# MD017A_ISO-F28027F_1.net
KiCad netlist of a schematic drawn in Altium Designer
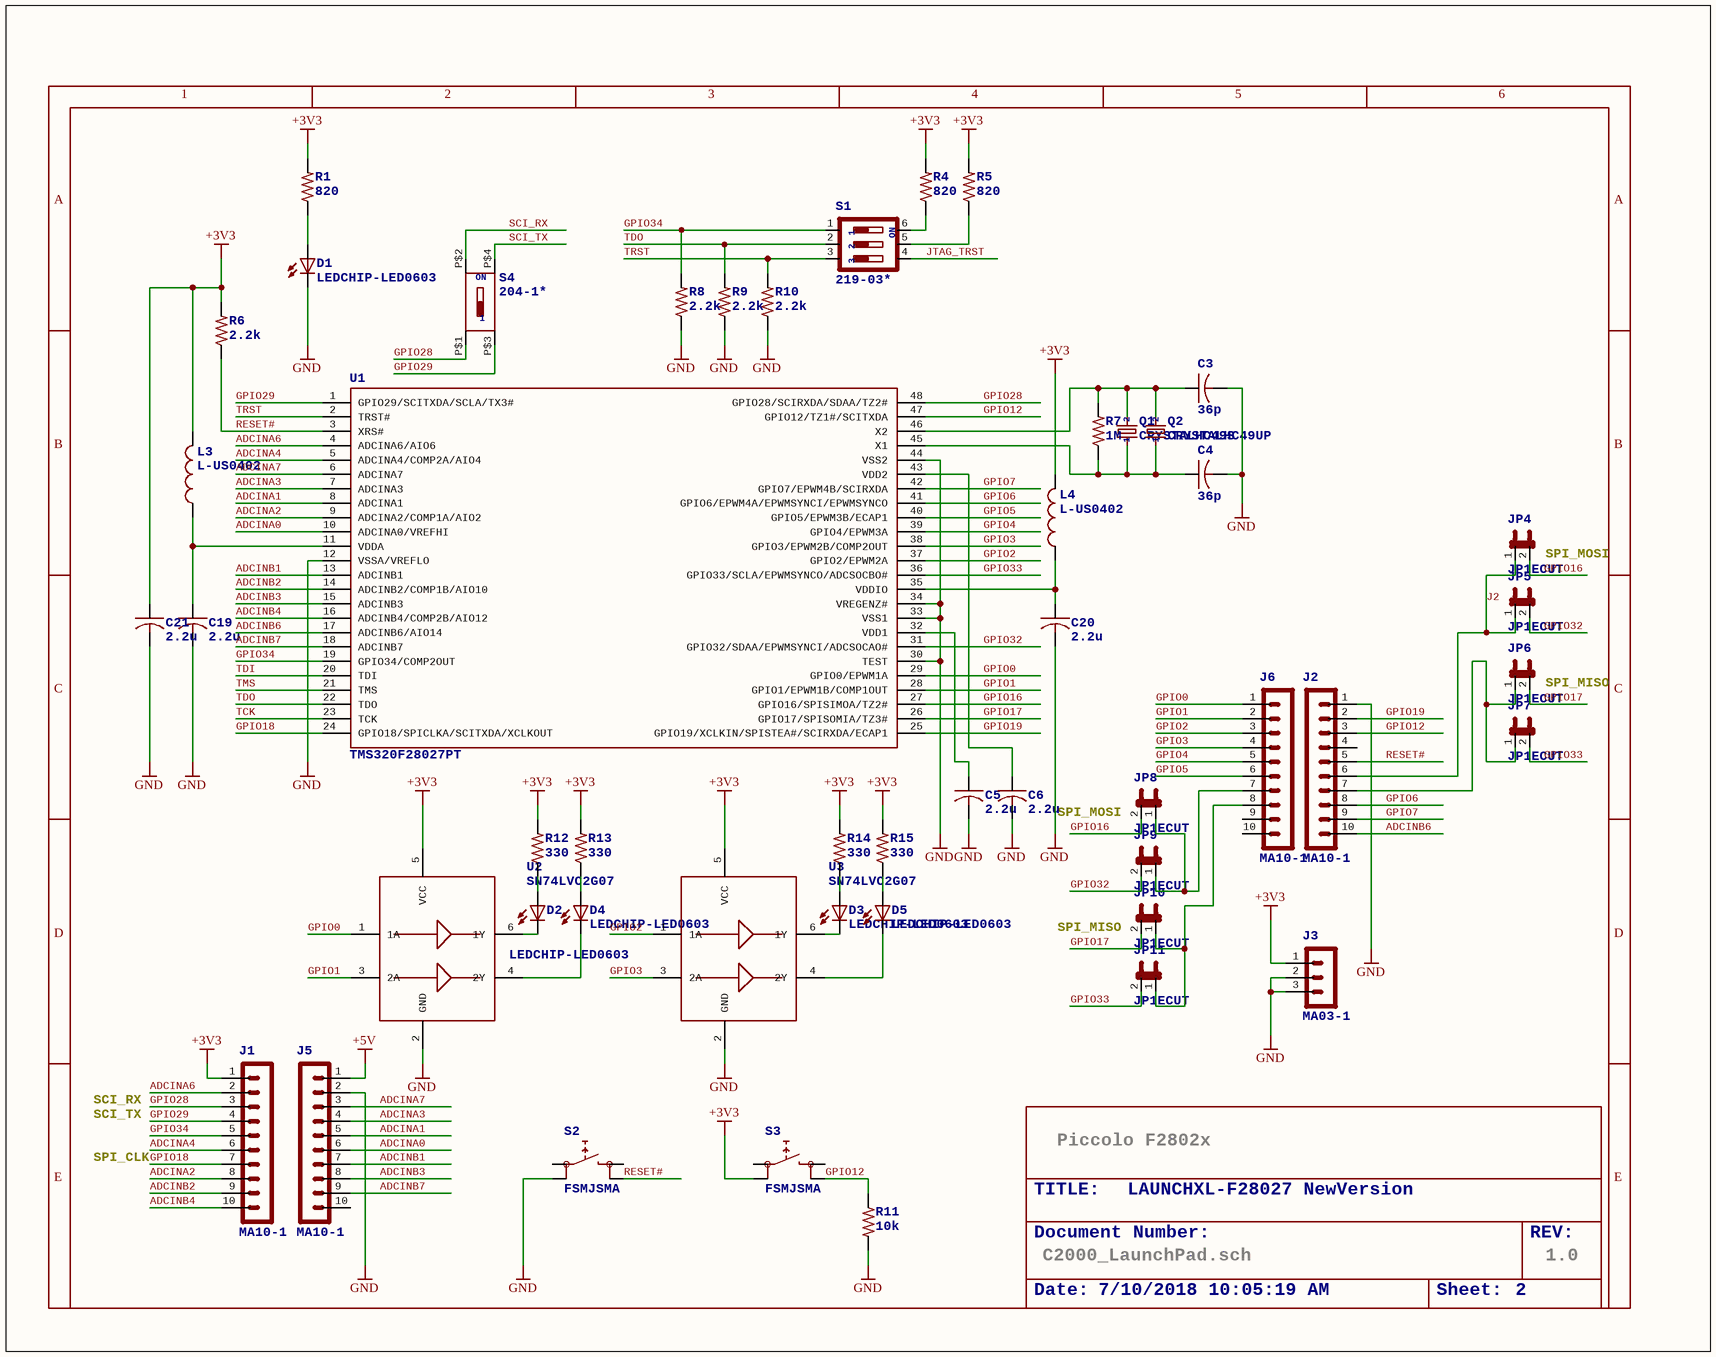
[diagram p0: MD017A ISO-F28027F_1.SchDoc]

(export (version "E")
  (design (tool "Eeschema 10.0.6"))
  (components
    (comp (ref "C3")
      (value "36p")
      (footprint "C0402")
      (description "CAPACITOR, American symbol")
      (libsource (lib "rcl") (part "C-USC0402"))
    )
    (comp (ref "C4")
      (value "36p")
      (footprint "C0402")
      (description "CAPACITOR, American symbol")
      (libsource (lib "rcl") (part "C-USC0402"))
    )
    (comp (ref "C5")
      (value "2.2u")
      (footprint "C0402")
      (description "CAPACITOR, American symbol")
      (libsource (lib "rcl") (part "C-USC0402"))
    )
    (comp (ref "C6")
      (value "2.2u")
      (footprint "C0402")
      (description "CAPACITOR, American symbol")
      (libsource (lib "rcl") (part "C-USC0402"))
    )
    (comp (ref "C19")
      (value "2.2u")
      (footprint "C0402")
      (description "CAPACITOR, American symbol")
      (libsource (lib "rcl") (part "C-USC0402"))
    )
    (comp (ref "C20")
      (value "2.2u")
      (footprint "C0402")
      (description "CAPACITOR, American symbol")
      (libsource (lib "rcl") (part "C-USC0402"))
    )
    (comp (ref "C21")
      (value "2.2u")
      (footprint "C0402")
      (description "CAPACITOR, American symbol")
      (libsource (lib "rcl") (part "C-USC0402"))
    )
    (comp (ref "D1")
      (value "LEDCHIP-LED0603")
      (footprint "CHIP-LED0603")
      (libsource (lib "led") (part "LEDCHIP-LED0603"))
    )
    (comp (ref "D2")
      (value "LEDCHIP-LED0603")
      (footprint "CHIP-LED0603")
      (libsource (lib "led") (part "LEDCHIP-LED0603"))
    )
    (comp (ref "D3")
      (value "LEDCHIP-LED0603")
      (footprint "CHIP-LED0603")
      (libsource (lib "led") (part "LEDCHIP-LED0603"))
    )
    (comp (ref "D4")
      (value "LEDCHIP-LED0603")
      (footprint "CHIP-LED0603")
      (libsource (lib "led") (part "LEDCHIP-LED0603"))
    )
    (comp (ref "D5")
      (value "LEDCHIP-LED0603")
      (footprint "CHIP-LED0603")
      (libsource (lib "led") (part "LEDCHIP-LED0603"))
    )
    (comp (ref "J1")
      (value "MA10-1")
      (footprint "MA10-1")
      (description "PIN HEADER")
      (libsource (lib "con-lstb") (part "MA10-1"))
    )
    (comp (ref "J2")
      (value "MA10-1")
      (footprint "MA10-1")
      (description "PIN HEADER")
      (libsource (lib "con-lstb") (part "MA10-1"))
    )
    (comp (ref "J3")
      (value "MA03-1")
      (footprint "MA03-1")
      (description "PIN HEADER")
      (libsource (lib "con-lstb") (part "MA03-1"))
    )
    (comp (ref "J5")
      (value "MA10-1")
      (footprint "MA10-1")
      (description "PIN HEADER")
      (libsource (lib "con-lstb") (part "MA10-1"))
    )
    (comp (ref "J6")
      (value "MA10-1")
      (footprint "MA10-1")
      (description "PIN HEADER")
      (libsource (lib "con-lstb") (part "MA10-1"))
    )
    (comp (ref "JP4")
      (value "JP1ECUT")
      (footprint "C0402")
      (description "JUMPER")
      (libsource (lib "jumper") (part "JP1ECUT"))
    )
    (comp (ref "JP5")
      (value "JP1ECUT")
      (footprint "C0402")
      (description "JUMPER")
      (libsource (lib "jumper") (part "JP1ECUT"))
    )
    (comp (ref "JP6")
      (value "JP1ECUT")
      (footprint "C0402")
      (description "JUMPER")
      (libsource (lib "jumper") (part "JP1ECUT"))
    )
    (comp (ref "JP7")
      (value "JP1ECUT")
      (footprint "C0402")
      (description "JUMPER")
      (libsource (lib "jumper") (part "JP1ECUT"))
    )
    (comp (ref "JP8")
      (value "JP1ECUT")
      (footprint "C0402")
      (description "JUMPER")
      (libsource (lib "jumper") (part "JP1ECUT"))
    )
    (comp (ref "JP9")
      (value "JP1ECUT")
      (footprint "C0402")
      (description "JUMPER")
      (libsource (lib "jumper") (part "JP1ECUT"))
    )
    (comp (ref "JP10")
      (value "JP1ECUT")
      (footprint "C0402")
      (description "JUMPER")
      (libsource (lib "jumper") (part "JP1ECUT"))
    )
    (comp (ref "JP11")
      (value "JP1ECUT")
      (footprint "C0402")
      (description "JUMPER")
      (libsource (lib "jumper") (part "JP1ECUT"))
    )
    (comp (ref "L3")
      (value "L-US0402")
      (footprint "R0402")
      (description "INDUCTOR, American symbol")
      (libsource (lib "rcl") (part "L-US0402"))
    )
    (comp (ref "L4")
      (value "L-US0402")
      (footprint "R0402")
      (description "INDUCTOR, American symbol")
      (libsource (lib "rcl") (part "L-US0402"))
    )
    (comp (ref "Q1")
      (value "CRYSTALHC49S")
      (footprint "HC49/S")
      (description "CRYSTAL")
      (fields (field (name "1") "1") (field (name "2") "2"))
      (libsource (lib "crystal") (part "CRYSTALHC49S"))
    )
    (comp (ref "Q2")
      (value "CRYSTALHC49UP")
      (footprint "HC49UP")
      (description "CRYSTAL")
      (fields (field (name "1") "1") (field (name "2") "2"))
      (libsource (lib "crystal") (part "CRYSTALHC49UP"))
    )
    (comp (ref "R1")
      (value "820")
      (footprint "R0402")
      (description "RESISTOR, American symbol")
      (libsource (lib "rcl") (part "R-US_R0402"))
    )
    (comp (ref "R4")
      (value "820")
      (footprint "R0402")
      (description "RESISTOR, American symbol")
      (libsource (lib "rcl") (part "R-US_R0402"))
    )
    (comp (ref "R5")
      (value "820")
      (footprint "R0402")
      (description "RESISTOR, American symbol")
      (libsource (lib "rcl") (part "R-US_R0402"))
    )
    (comp (ref "R6")
      (value "2.2k")
      (footprint "R0402")
      (description "RESISTOR, American symbol")
      (libsource (lib "rcl") (part "R-US_R0402"))
    )
    (comp (ref "R7")
      (value "1M")
      (footprint "R0402")
      (description "RESISTOR, American symbol")
      (libsource (lib "rcl") (part "R-US_R0402"))
    )
    (comp (ref "R8")
      (value "2.2k")
      (footprint "R0402")
      (description "RESISTOR, American symbol")
      (libsource (lib "rcl") (part "R-US_R0402"))
    )
    (comp (ref "R9")
      (value "2.2k")
      (footprint "R0402")
      (description "RESISTOR, American symbol")
      (libsource (lib "rcl") (part "R-US_R0402"))
    )
    (comp (ref "R10")
      (value "2.2k")
      (footprint "R0402")
      (description "RESISTOR, American symbol")
      (libsource (lib "rcl") (part "R-US_R0402"))
    )
    (comp (ref "R11")
      (value "10k")
      (footprint "R0402")
      (description "RESISTOR, American symbol")
      (libsource (lib "rcl") (part "R-US_R0402"))
    )
    (comp (ref "R12")
      (value "330")
      (footprint "R0402")
      (description "RESISTOR, American symbol")
      (libsource (lib "rcl") (part "R-US_R0402"))
    )
    (comp (ref "R13")
      (value "330")
      (footprint "R0402")
      (description "RESISTOR, American symbol")
      (libsource (lib "rcl") (part "R-US_R0402"))
    )
    (comp (ref "R14")
      (value "330")
      (footprint "R0402")
      (description "RESISTOR, American symbol")
      (libsource (lib "rcl") (part "R-US_R0402"))
    )
    (comp (ref "R15")
      (value "330")
      (footprint "R0402")
      (description "RESISTOR, American symbol")
      (libsource (lib "rcl") (part "R-US_R0402"))
    )
    (comp (ref "S1")
      (value "219-03*")
      (footprint "CTS-219-03")
      (description "Surface Mount DIP Switch Series 219 SMT   CTS Electronic Components Sourc: www.ctscorp.com")
      (fields (field (name "1") "1") (field (name "2") "2") (field (name "3") "3") (field (name "ON") "ON"))
      (libsource (lib "switch-dil") (part "219-03*"))
    )
    (comp (ref "S2") (value "FSMJSMA") (footprint "FSMJSMA") (libsource (lib "switch") (part "FSMJSMA")))
    (comp (ref "S3") (value "FSMJSMA") (footprint "FSMJSMA") (libsource (lib "switch") (part "FSMJSMA")))
    (comp (ref "S4")
      (value "204-1*")
      (footprint "CTS-204-1")
      (fields (field (name "1") "1") (field (name "ON") "ON"))
      (libsource (lib "switch-dil") (part "204-1*"))
    )
    (comp (ref "U1")
      (value "TMS320F28027PT")
      (footprint "PQFP48")
      (libsource (lib "texas") (part "TMS320F28027PT"))
    )
    (comp (ref "U2")
      (value "SN74LVC2G07")
      (footprint "SOT23-6-DBV")
      (libsource (lib "texas") (part "SN74LVC2G07"))
    )
    (comp (ref "U3")
      (value "SN74LVC2G07")
      (footprint "SOT23-6-DBV")
      (libsource (lib "texas") (part "SN74LVC2G07"))
    )
  )
  (nets
    (net (code "1") (name "+3V3") (class "Default")
      (node (ref "C21") (pin "1") (pinfunction "1_1") (pintype "passive"))
      (node (ref "J1") (pin "1") (pinfunction "1_1") (pintype "passive"))
      (node (ref "J3") (pin "1") (pinfunction "1_1") (pintype "passive"))
      (node (ref "L3") (pin "2") (pinfunction "2_2") (pintype "passive"))
      (node (ref "L4") (pin "2") (pinfunction "2_2") (pintype "passive"))
      (node (ref "R1") (pin "2") (pinfunction "2_2") (pintype "passive"))
      (node (ref "R12") (pin "2") (pinfunction "2_2") (pintype "passive"))
      (node (ref "R13") (pin "2") (pinfunction "2_2") (pintype "passive"))
      (node (ref "R14") (pin "2") (pinfunction "2_2") (pintype "passive"))
      (node (ref "R15") (pin "2") (pinfunction "2_2") (pintype "passive"))
      (node (ref "R4") (pin "2") (pinfunction "2_2") (pintype "passive"))
      (node (ref "R5") (pin "2") (pinfunction "2_2") (pintype "passive"))
      (node (ref "R6") (pin "2") (pinfunction "2_2") (pintype "passive"))
      (node (ref "S3") (pin "P$2") (pinfunction "0_P$2") (pintype "passive"))
      (node (ref "U2") (pin "5") (pinfunction "VCC_5") (pintype "passive"))
      (node (ref "U3") (pin "5") (pinfunction "VCC_5") (pintype "passive"))
    )
    (net (code "2") (name "+5V") (class "Default")
      (node (ref "J5") (pin "1") (pinfunction "1_1") (pintype "passive"))
    )
    (net (code "3") (name "/ADCINA0") (class "Default")
      (node (ref "J5") (pin "6") (pinfunction "6_6") (pintype "passive"))
      (node (ref "U1") (pin "10") (pinfunction "ADCINA0/VREFHI_10") (pintype "passive"))
    )
    (net (code "4") (name "/ADCINA1") (class "Default")
      (node (ref "J5") (pin "5") (pinfunction "5_5") (pintype "passive"))
      (node (ref "U1") (pin "8") (pinfunction "ADCINA1_8") (pintype "passive"))
    )
    (net (code "5") (name "/ADCINA2") (class "Default")
      (node (ref "J1") (pin "8") (pinfunction "8_8") (pintype "passive"))
      (node (ref "U1") (pin "9") (pinfunction "ADCINA2/COMP1A/AIO2_9") (pintype "passive"))
    )
    (net (code "6") (name "/ADCINA3") (class "Default")
      (node (ref "J5") (pin "4") (pinfunction "4_4") (pintype "passive"))
      (node (ref "U1") (pin "7") (pinfunction "ADCINA3_7") (pintype "passive"))
    )
    (net (code "7") (name "/ADCINA4") (class "Default")
      (node (ref "J1") (pin "6") (pinfunction "6_6") (pintype "passive"))
      (node (ref "U1") (pin "5") (pinfunction "ADCINA4/COMP2A/AIO4_5") (pintype "passive"))
    )
    (net (code "8") (name "/ADCINA6") (class "Default")
      (node (ref "J1") (pin "2") (pinfunction "2_2") (pintype "passive"))
      (node (ref "U1") (pin "4") (pinfunction "ADCINA6/AIO6_4") (pintype "passive"))
    )
    (net (code "9") (name "/ADCINA7") (class "Default")
      (node (ref "J5") (pin "3") (pinfunction "3_3") (pintype "passive"))
      (node (ref "U1") (pin "6") (pinfunction "ADCINA7_6") (pintype "passive"))
    )
    (net (code "10") (name "/ADCINB1") (class "Default")
      (node (ref "J5") (pin "7") (pinfunction "7_7") (pintype "passive"))
      (node (ref "U1") (pin "13") (pinfunction "ADCINB1_13") (pintype "passive"))
    )
    (net (code "11") (name "/ADCINB2") (class "Default")
      (node (ref "J1") (pin "9") (pinfunction "9_9") (pintype "passive"))
      (node (ref "U1") (pin "14") (pinfunction "ADCINB2/COMP1B/AIO10_14") (pintype "passive"))
    )
    (net (code "12") (name "/ADCINB3") (class "Default")
      (node (ref "J5") (pin "8") (pinfunction "8_8") (pintype "passive"))
      (node (ref "U1") (pin "15") (pinfunction "ADCINB3_15") (pintype "passive"))
    )
    (net (code "13") (name "/ADCINB4") (class "Default")
      (node (ref "J1") (pin "10") (pinfunction "10_10") (pintype "passive"))
      (node (ref "U1") (pin "16") (pinfunction "ADCINB4/COMP2B/AIO12_16") (pintype "passive"))
    )
    (net (code "14") (name "/ADCINB6") (class "Default")
      (node (ref "J2") (pin "10") (pinfunction "10_10") (pintype "passive"))
      (node (ref "U1") (pin "17") (pinfunction "ADCINB6/AIO14_17") (pintype "passive"))
    )
    (net (code "15") (name "/ADCINB7") (class "Default")
      (node (ref "J5") (pin "9") (pinfunction "9_9") (pintype "passive"))
      (node (ref "U1") (pin "18") (pinfunction "ADCINB7_18") (pintype "passive"))
    )
    (net (code "16") (name "/GPIO0") (class "Default")
      (node (ref "J6") (pin "1") (pinfunction "1_1") (pintype "passive"))
      (node (ref "U1") (pin "29") (pinfunction "GPIO0/EPWM1A_29") (pintype "passive"))
      (node (ref "U2") (pin "1") (pinfunction "1A_1") (pintype "passive"))
    )
    (net (code "17") (name "/GPIO1") (class "Default")
      (node (ref "J6") (pin "2") (pinfunction "2_2") (pintype "passive"))
      (node (ref "U1") (pin "28") (pinfunction "GPIO1/EPWM1B/COMP1OUT_28") (pintype "passive"))
      (node (ref "U2") (pin "3") (pinfunction "2A_3") (pintype "passive"))
    )
    (net (code "18") (name "/GPIO2") (class "Default")
      (node (ref "J6") (pin "3") (pinfunction "3_3") (pintype "passive"))
      (node (ref "U1") (pin "37") (pinfunction "GPIO2/EPWM2A_37") (pintype "passive"))
      (node (ref "U3") (pin "1") (pinfunction "1A_1") (pintype "passive"))
    )
    (net (code "19") (name "/GPIO3") (class "Default")
      (node (ref "J6") (pin "4") (pinfunction "4_4") (pintype "passive"))
      (node (ref "U1") (pin "38") (pinfunction "GPIO3/EPWM2B/COMP2OUT_38") (pintype "passive"))
      (node (ref "U3") (pin "3") (pinfunction "2A_3") (pintype "passive"))
    )
    (net (code "20") (name "/GPIO4") (class "Default")
      (node (ref "J6") (pin "5") (pinfunction "5_5") (pintype "passive"))
      (node (ref "U1") (pin "39") (pinfunction "GPIO4/EPWM3A_39") (pintype "passive"))
    )
    (net (code "21") (name "/GPIO5") (class "Default")
      (node (ref "J6") (pin "6") (pinfunction "6_6") (pintype "passive"))
      (node (ref "U1") (pin "40") (pinfunction "GPIO5/EPWM3B/ECAP1_40") (pintype "passive"))
    )
    (net (code "22") (name "/GPIO6") (class "Default")
      (node (ref "J2") (pin "8") (pinfunction "8_8") (pintype "passive"))
      (node (ref "U1") (pin "41") (pinfunction "GPIO6/EPWM4A/EPWMSYNCI/EPWMSYNCO_41") (pintype "passive"))
    )
    (net (code "23") (name "/GPIO7") (class "Default")
      (node (ref "J2") (pin "9") (pinfunction "9_9") (pintype "passive"))
      (node (ref "U1") (pin "42") (pinfunction "GPIO7/EPWM4B/SCIRXDA_42") (pintype "passive"))
    )
    (net (code "24") (name "/GPIO12") (class "Default")
      (node (ref "J2") (pin "3") (pinfunction "3_3") (pintype "passive"))
      (node (ref "R11") (pin "1") (pinfunction "1_1") (pintype "passive"))
      (node (ref "S3") (pin "P$4") (pinfunction "1_P$4") (pintype "passive"))
      (node (ref "U1") (pin "47") (pinfunction "GPIO12/TZ1#/SCITXDA_47") (pintype "passive"))
    )
    (net (code "25") (name "/GPIO16") (class "Default")
      (node (ref "JP4") (pin "2") (pinfunction "2_2") (pintype "passive"))
      (node (ref "JP8") (pin "2") (pinfunction "2_2") (pintype "passive"))
      (node (ref "U1") (pin "27") (pinfunction "GPIO16/SPISIMOA/TZ2#_27") (pintype "passive"))
    )
    (net (code "26") (name "/GPIO17") (class "Default")
      (node (ref "JP10") (pin "2") (pinfunction "2_2") (pintype "passive"))
      (node (ref "JP6") (pin "2") (pinfunction "2_2") (pintype "passive"))
      (node (ref "U1") (pin "26") (pinfunction "GPIO17/SPISOMIA/TZ3#_26") (pintype "passive"))
    )
    (net (code "27") (name "/GPIO18") (class "Default")
      (node (ref "J1") (pin "7") (pinfunction "7_7") (pintype "passive"))
      (node (ref "U1") (pin "24") (pinfunction "GPIO18/SPICLKA/SCITXDA/XCLKOUT_24") (pintype "passive"))
    )
    (net (code "28") (name "/GPIO19") (class "Default")
      (node (ref "J2") (pin "2") (pinfunction "2_2") (pintype "passive"))
      (node (ref "U1") (pin "25") (pinfunction "GPIO19/XCLKIN/SPISTEA#/SCIRXDA/ECAP1_25") (pintype "passive"))
    )
    (net (code "29") (name "/GPIO28") (class "Default")
      (node (ref "J1") (pin "3") (pinfunction "3_3") (pintype "passive"))
      (node (ref "S4") (pin "P$1") (pinfunction "1_P$1") (pintype "passive"))
      (node (ref "U1") (pin "48") (pinfunction "GPIO28/SCIRXDA/SDAA/TZ2#_48") (pintype "passive"))
    )
    (net (code "30") (name "/GPIO29") (class "Default")
      (node (ref "J1") (pin "4") (pinfunction "4_4") (pintype "passive"))
      (node (ref "S4") (pin "P$3") (pinfunction "3_P$3") (pintype "passive"))
      (node (ref "U1") (pin "1") (pinfunction "GPIO29/SCITXDA/SCLA/TX3#_1") (pintype "passive"))
    )
    (net (code "31") (name "/GPIO32") (class "Default")
      (node (ref "JP5") (pin "2") (pinfunction "2_2") (pintype "passive"))
      (node (ref "JP9") (pin "2") (pinfunction "2_2") (pintype "passive"))
      (node (ref "U1") (pin "31") (pinfunction "GPIO32/SDAA/EPWMSYNCI/ADCSOCAO#_31") (pintype "passive"))
    )
    (net (code "32") (name "/GPIO33") (class "Default")
      (node (ref "JP11") (pin "2") (pinfunction "2_2") (pintype "passive"))
      (node (ref "JP7") (pin "2") (pinfunction "2_2") (pintype "passive"))
      (node (ref "U1") (pin "36") (pinfunction "GPIO33/SCLA/EPWMSYNCO/ADCSOCBO#_36") (pintype "passive"))
    )
    (net (code "33") (name "/GPIO34") (class "Default")
      (node (ref "J1") (pin "5") (pinfunction "5_5") (pintype "passive"))
      (node (ref "R8") (pin "2") (pinfunction "2_2") (pintype "passive"))
      (node (ref "S1") (pin "1") (pinfunction "1_1") (pintype "passive"))
      (node (ref "U1") (pin "19") (pinfunction "GPIO34/COMP2OUT_19") (pintype "passive"))
    )
    (net (code "34") (name "/J2") (class "Default")
      (node (ref "J2") (pin "6") (pinfunction "6_6") (pintype "passive"))
      (node (ref "JP4") (pin "1") (pinfunction "1_1") (pintype "passive"))
      (node (ref "JP5") (pin "1") (pinfunction "1_1") (pintype "passive"))
    )
    (net (code "35") (name "/JTAG_TRST") (class "Default")
      (node (ref "S1") (pin "4") (pinfunction "4_4") (pintype "passive"))
    )
    (net (code "36") (name "/RESET#") (class "Default")
      (node (ref "J2") (pin "5") (pinfunction "5_5") (pintype "passive"))
      (node (ref "R6") (pin "1") (pinfunction "1_1") (pintype "passive"))
      (node (ref "S2") (pin "P$4") (pinfunction "1_P$4") (pintype "passive"))
      (node (ref "U1") (pin "3") (pinfunction "XRS#_3") (pintype "passive"))
    )
    (net (code "37") (name "/SCI_RX") (class "Default")
      (node (ref "S4") (pin "P$2") (pinfunction "2_P$2") (pintype "passive"))
    )
    (net (code "38") (name "/SCI_TX") (class "Default")
      (node (ref "S4") (pin "P$4") (pinfunction "4_P$4") (pintype "passive"))
    )
    (net (code "39") (name "/TCK") (class "Default")
      (node (ref "U1") (pin "23") (pinfunction "TCK_23") (pintype "passive"))
    )
    (net (code "40") (name "/TDI") (class "Default")
      (node (ref "U1") (pin "20") (pinfunction "TDI_20") (pintype "passive"))
    )
    (net (code "41") (name "/TDO") (class "Default")
      (node (ref "R9") (pin "2") (pinfunction "2_2") (pintype "passive"))
      (node (ref "S1") (pin "2") (pinfunction "2_2") (pintype "passive"))
      (node (ref "U1") (pin "22") (pinfunction "TDO_22") (pintype "passive"))
    )
    (net (code "42") (name "/TMS") (class "Default")
      (node (ref "U1") (pin "21") (pinfunction "TMS_21") (pintype "passive"))
    )
    (net (code "43") (name "/TRST") (class "Default")
      (node (ref "R10") (pin "2") (pinfunction "2_2") (pintype "passive"))
      (node (ref "S1") (pin "3") (pinfunction "3_3") (pintype "passive"))
      (node (ref "U1") (pin "2") (pinfunction "TRST#_2") (pintype "passive"))
    )
    (net (code "44") (name "GND") (class "Default")
      (node (ref "C19") (pin "2") (pinfunction "2_2") (pintype "passive"))
      (node (ref "C20") (pin "2") (pinfunction "2_2") (pintype "passive"))
      (node (ref "C21") (pin "2") (pinfunction "2_2") (pintype "passive"))
      (node (ref "C3") (pin "2") (pinfunction "2_2") (pintype "passive"))
      (node (ref "C4") (pin "2") (pinfunction "2_2") (pintype "passive"))
      (node (ref "C5") (pin "2") (pinfunction "2_2") (pintype "passive"))
      (node (ref "C6") (pin "2") (pinfunction "2_2") (pintype "passive"))
      (node (ref "D1") (pin "C") (pinfunction "C_C") (pintype "passive"))
      (node (ref "J2") (pin "1") (pinfunction "1_1") (pintype "passive"))
      (node (ref "J3") (pin "2") (pinfunction "2_2") (pintype "passive"))
      (node (ref "J3") (pin "3") (pinfunction "3_3") (pintype "passive"))
      (node (ref "J5") (pin "2") (pinfunction "2_2") (pintype "passive"))
      (node (ref "R10") (pin "1") (pinfunction "1_1") (pintype "passive"))
      (node (ref "R11") (pin "2") (pinfunction "2_2") (pintype "passive"))
      (node (ref "R8") (pin "1") (pinfunction "1_1") (pintype "passive"))
      (node (ref "R9") (pin "1") (pinfunction "1_1") (pintype "passive"))
      (node (ref "S2") (pin "P$2") (pinfunction "0_P$2") (pintype "passive"))
      (node (ref "U1") (pin "12") (pinfunction "VSSA/VREFLO_12") (pintype "passive"))
      (node (ref "U1") (pin "30") (pinfunction "TEST_30") (pintype "passive"))
      (node (ref "U1") (pin "33") (pinfunction "VSS1_33") (pintype "passive"))
      (node (ref "U1") (pin "34") (pinfunction "VREGENZ#_34") (pintype "passive"))
      (node (ref "U1") (pin "44") (pinfunction "VSS2_44") (pintype "passive"))
      (node (ref "U2") (pin "2") (pinfunction "GND_2") (pintype "passive"))
      (node (ref "U3") (pin "2") (pinfunction "GND_2") (pintype "passive"))
    )
    (net (code "45") (name "Net-(D1-PadA)") (class "Default")
      (node (ref "D1") (pin "A") (pinfunction "A_A") (pintype "passive"))
      (node (ref "R1") (pin "1") (pinfunction "1_1") (pintype "passive"))
    )
    (net (code "46") (name "Net-(D2-PadA)") (class "Default")
      (node (ref "D2") (pin "A") (pinfunction "A_A") (pintype "passive"))
      (node (ref "R12") (pin "1") (pinfunction "1_1") (pintype "passive"))
    )
    (net (code "47") (name "Net-(D3-PadA)") (class "Default")
      (node (ref "D3") (pin "A") (pinfunction "A_A") (pintype "passive"))
      (node (ref "R14") (pin "1") (pinfunction "1_1") (pintype "passive"))
    )
    (net (code "48") (name "Net-(D4-PadA)") (class "Default")
      (node (ref "D4") (pin "A") (pinfunction "A_A") (pintype "passive"))
      (node (ref "R13") (pin "1") (pinfunction "1_1") (pintype "passive"))
    )
    (net (code "49") (name "Net-(D5-PadA)") (class "Default")
      (node (ref "D5") (pin "A") (pinfunction "A_A") (pintype "passive"))
      (node (ref "R15") (pin "1") (pinfunction "1_1") (pintype "passive"))
    )
    (net (code "50") (name "Net-(J2-Pad7)") (class "Default")
      (node (ref "J2") (pin "7") (pinfunction "7_7") (pintype "passive"))
      (node (ref "JP6") (pin "1") (pinfunction "1_1") (pintype "passive"))
      (node (ref "JP7") (pin "1") (pinfunction "1_1") (pintype "passive"))
    )
    (net (code "51") (name "Net-(J6-Pad7)") (class "Default")
      (node (ref "J6") (pin "7") (pinfunction "7_7") (pintype "passive"))
      (node (ref "JP8") (pin "1") (pinfunction "1_1") (pintype "passive"))
      (node (ref "JP9") (pin "1") (pinfunction "1_1") (pintype "passive"))
    )
    (net (code "52") (name "Net-(J6-Pad8)") (class "Default")
      (node (ref "J6") (pin "8") (pinfunction "8_8") (pintype "passive"))
      (node (ref "JP10") (pin "1") (pinfunction "1_1") (pintype "passive"))
      (node (ref "JP11") (pin "1") (pinfunction "1_1") (pintype "passive"))
    )
    (net (code "53") (name "Net-(R4-Pad1)") (class "Default")
      (node (ref "R4") (pin "1") (pinfunction "1_1") (pintype "passive"))
      (node (ref "S1") (pin "6") (pinfunction "6_6") (pintype "passive"))
    )
    (net (code "54") (name "Net-(R5-Pad1)") (class "Default")
      (node (ref "R5") (pin "1") (pinfunction "1_1") (pintype "passive"))
      (node (ref "S1") (pin "5") (pinfunction "5_5") (pintype "passive"))
    )
    (net (code "55") (name "Net-(U1-VDD1)") (class "Default")
      (node (ref "C5") (pin "1") (pinfunction "1_1") (pintype "passive"))
      (node (ref "U1") (pin "32") (pinfunction "VDD1_32") (pintype "passive"))
    )
    (net (code "56") (name "Net-(U1-VDD2)") (class "Default")
      (node (ref "C6") (pin "1") (pinfunction "1_1") (pintype "passive"))
      (node (ref "U1") (pin "43") (pinfunction "VDD2_43") (pintype "passive"))
    )
    (net (code "57") (name "Net-(U1-VDDA)") (class "Default")
      (node (ref "C19") (pin "1") (pinfunction "1_1") (pintype "passive"))
      (node (ref "L3") (pin "1") (pinfunction "1_1") (pintype "passive"))
      (node (ref "U1") (pin "11") (pinfunction "VDDA_11") (pintype "passive"))
    )
    (net (code "58") (name "Net-(U1-VDDIO)") (class "Default")
      (node (ref "C20") (pin "1") (pinfunction "1_1") (pintype "passive"))
      (node (ref "L4") (pin "1") (pinfunction "1_1") (pintype "passive"))
      (node (ref "U1") (pin "35") (pinfunction "VDDIO_35") (pintype "passive"))
    )
    (net (code "59") (name "Net-(U1-X1)") (class "Default")
      (node (ref "C4") (pin "1") (pinfunction "1_1") (pintype "passive"))
      (node (ref "Q1") (pin "1") (pinfunction "1_1") (pintype "passive"))
      (node (ref "Q2") (pin "1") (pinfunction "1_1") (pintype "passive"))
      (node (ref "R7") (pin "1") (pinfunction "1_1") (pintype "passive"))
      (node (ref "U1") (pin "45") (pinfunction "X1_45") (pintype "passive"))
    )
    (net (code "60") (name "Net-(U1-X2)") (class "Default")
      (node (ref "C3") (pin "1") (pinfunction "1_1") (pintype "passive"))
      (node (ref "Q1") (pin "2") (pinfunction "2_2") (pintype "passive"))
      (node (ref "Q2") (pin "2") (pinfunction "2_2") (pintype "passive"))
      (node (ref "R7") (pin "2") (pinfunction "2_2") (pintype "passive"))
      (node (ref "U1") (pin "46") (pinfunction "X2_46") (pintype "passive"))
    )
    (net (code "61") (name "Net-(U2-1Y)") (class "Default")
      (node (ref "D2") (pin "C") (pinfunction "C_C") (pintype "passive"))
      (node (ref "U2") (pin "6") (pinfunction "1Y_6") (pintype "passive"))
    )
    (net (code "62") (name "Net-(U2-2Y)") (class "Default")
      (node (ref "D4") (pin "C") (pinfunction "C_C") (pintype "passive"))
      (node (ref "U2") (pin "4") (pinfunction "2Y_4") (pintype "passive"))
    )
    (net (code "63") (name "Net-(U3-1Y)") (class "Default")
      (node (ref "D3") (pin "C") (pinfunction "C_C") (pintype "passive"))
      (node (ref "U3") (pin "6") (pinfunction "1Y_6") (pintype "passive"))
    )
    (net (code "64") (name "Net-(U3-2Y)") (class "Default")
      (node (ref "D5") (pin "C") (pinfunction "C_C") (pintype "passive"))
      (node (ref "U3") (pin "4") (pinfunction "2Y_4") (pintype "passive"))
    )
    (net (code "65") (name "unconnected-(J2-Pad4)") (class "Default")
      (node (ref "J2") (pin "4") (pinfunction "4_4") (pintype "passive"))
    )
    (net (code "66") (name "unconnected-(J5-Pad10)") (class "Default")
      (node (ref "J5") (pin "10") (pinfunction "10_10") (pintype "passive"))
    )
    (net (code "67") (name "unconnected-(J6-Pad9)") (class "Default")
      (node (ref "J6") (pin "9") (pinfunction "9_9") (pintype "passive"))
    )
    (net (code "68") (name "unconnected-(J6-Pad10)") (class "Default")
      (node (ref "J6") (pin "10") (pinfunction "10_10") (pintype "passive"))
    )
    (net (code "69") (name "unconnected-(S2-0-PadP$1)") (class "Default")
      (node (ref "S2") (pin "P$1") (pinfunction "0_P$1") (pintype "passive"))
    )
    (net (code "70") (name "unconnected-(S2-1-PadP$3)") (class "Default")
      (node (ref "S2") (pin "P$3") (pinfunction "1_P$3") (pintype "passive"))
    )
    (net (code "71") (name "unconnected-(S3-0-PadP$1)") (class "Default")
      (node (ref "S3") (pin "P$1") (pinfunction "0_P$1") (pintype "passive"))
    )
    (net (code "72") (name "unconnected-(S3-1-PadP$3)") (class "Default")
      (node (ref "S3") (pin "P$3") (pinfunction "1_P$3") (pintype "passive"))
    )
  )
)
